# jtag_levelxlate.net
KiCad netlist of a schematic drawn in Altium Designer
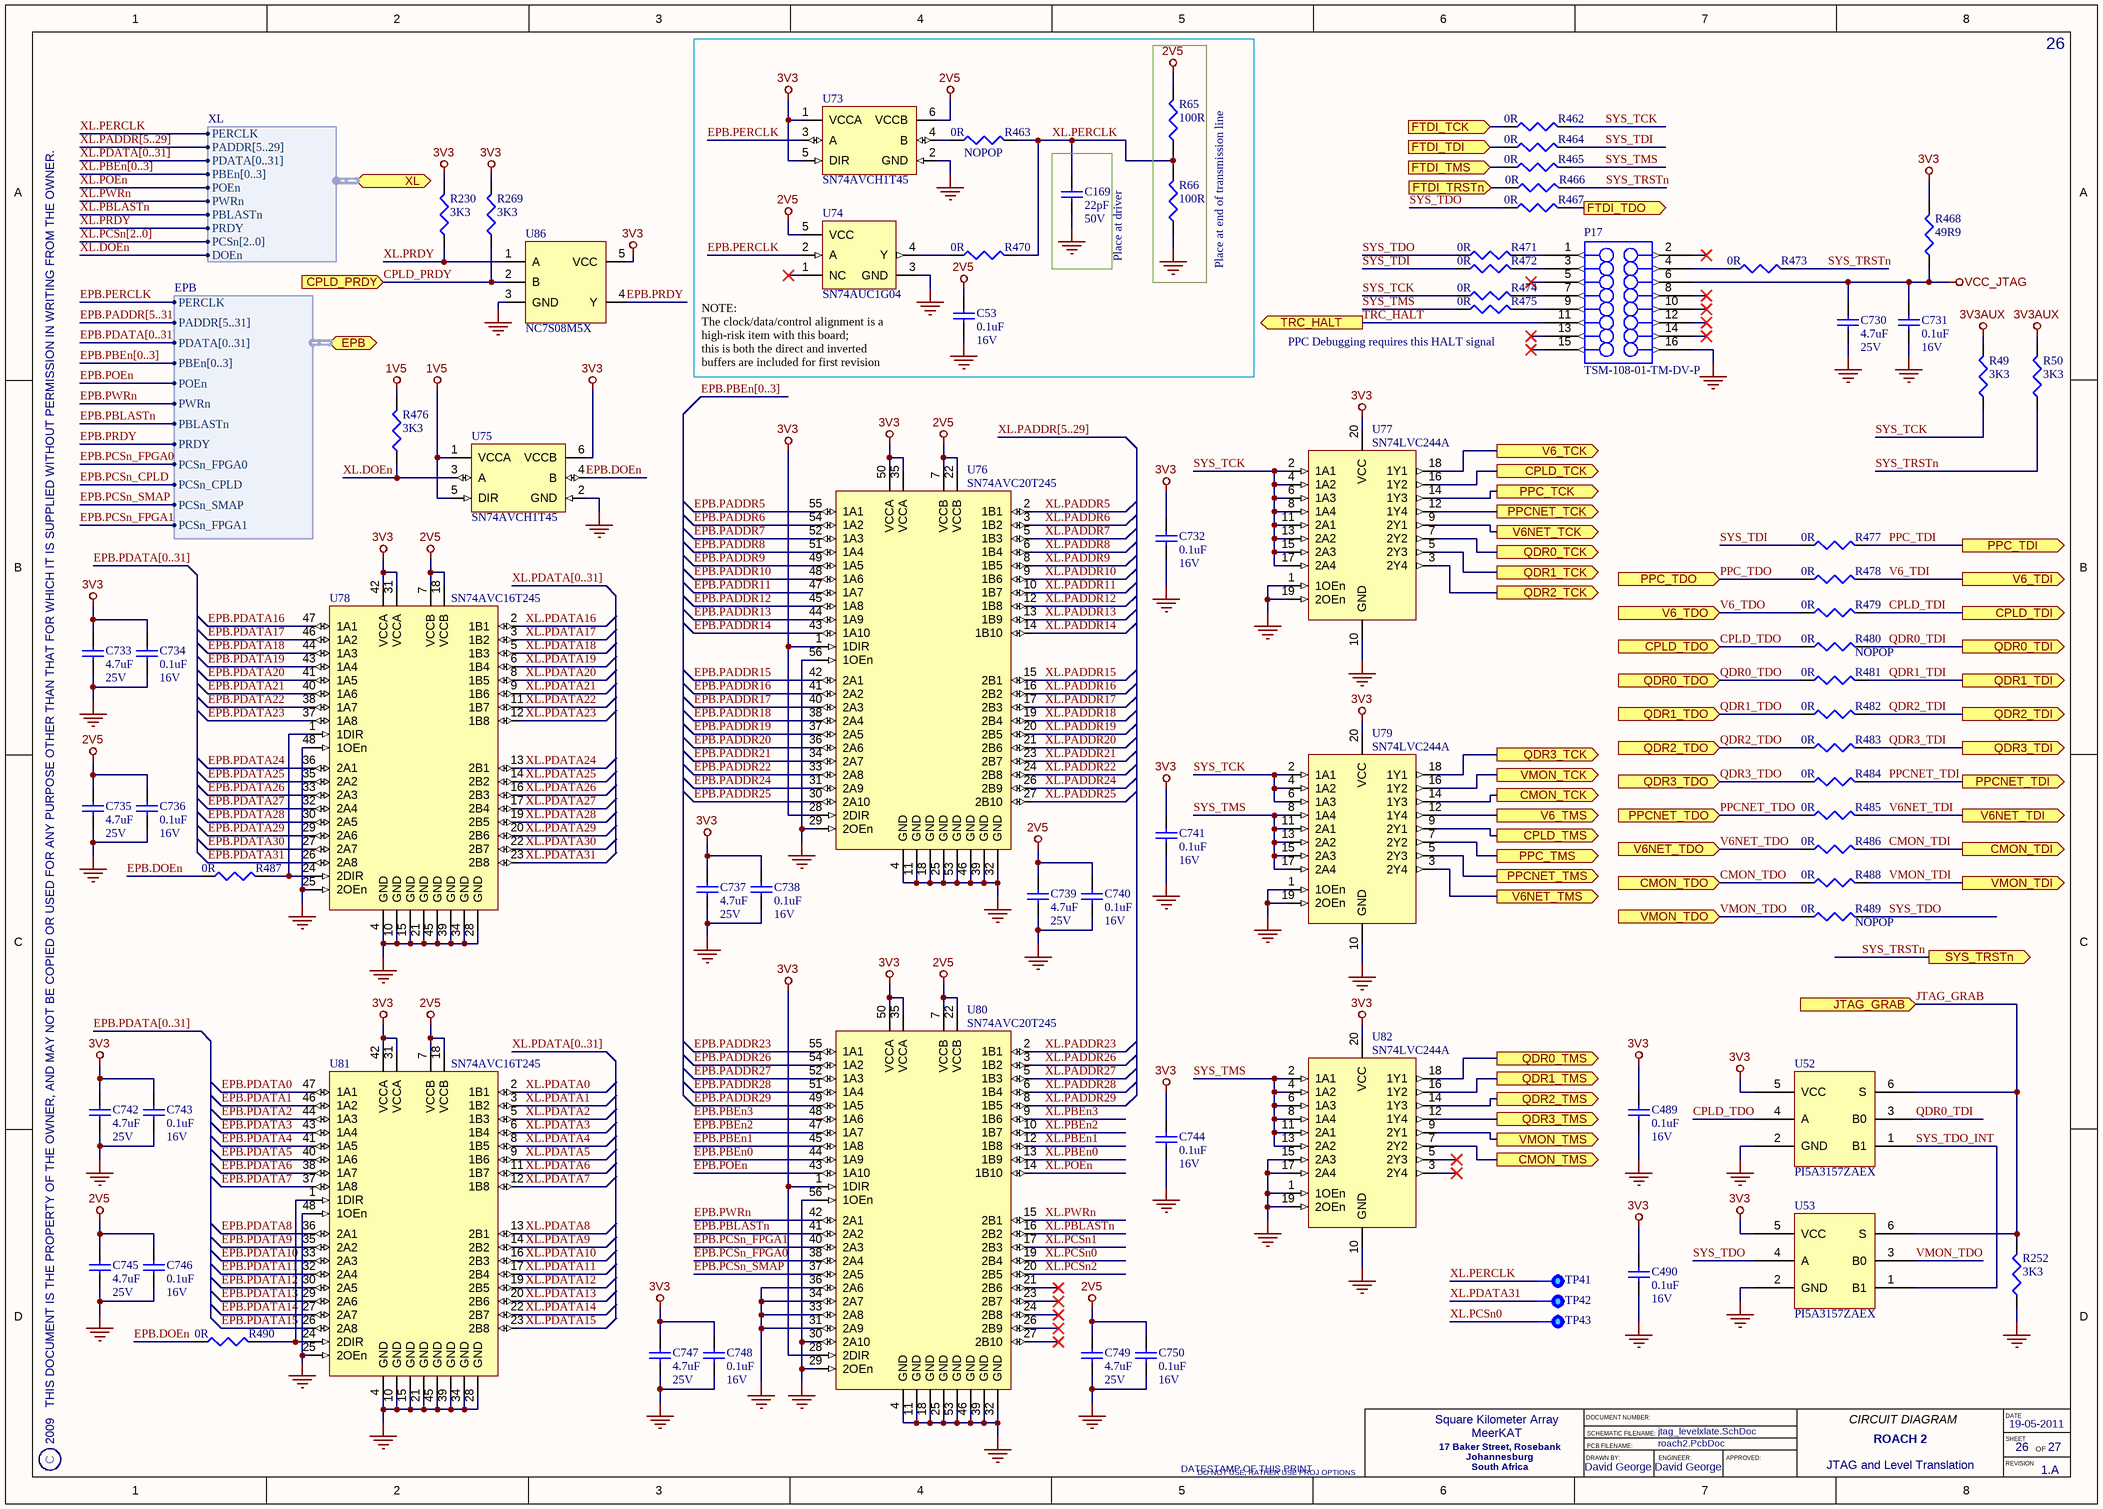
[diagram p0: jtag_levelxlate.SchDoc]

(export (version "E")
  (design (tool "Eeschema 10.0.6"))
  (components
    (comp (ref "C53")
      (value "0.1uF")
      (footprint "CAPC1005X60L")
      (description "0.1uF, Ceramic Capacitor")
      (fields
        (field (name "RATING") "16V")
        (field (name "MANUFACTURER") "VENKEL")
        (field (name "PARTNUM") "C0402X7R160-104KN")
      )
      (libsource (lib "altium_db") (part "CapStd"))
    )
    (comp (ref "C169")
      (value "22pF")
      (footprint "CAPC1005X55L")
      (description "22pF, Ceramic Capacitor")
      (fields
        (field (name "RATING") "50V")
        (field (name "MANUFACTURER") "MURATA")
        (field (name "PARTNUM") "GRM1555C1H220JZ01D")
      )
      (libsource (lib "altium_db") (part "CapStd"))
    )
    (comp (ref "C489")
      (value "0.1uF")
      (footprint "CAPC1005X60L")
      (description "0.1uF, Ceramic Capacitor")
      (fields
        (field (name "RATING") "16V")
        (field (name "MANUFACTURER") "VENKEL")
        (field (name "PARTNUM") "C0402X7R160-104KN")
      )
      (libsource (lib "altium_db") (part "CapStd"))
    )
    (comp (ref "C490")
      (value "0.1uF")
      (footprint "CAPC1005X60L")
      (description "0.1uF, Ceramic Capacitor")
      (fields
        (field (name "RATING") "16V")
        (field (name "MANUFACTURER") "VENKEL")
        (field (name "PARTNUM") "C0402X7R160-104KN")
      )
      (libsource (lib "altium_db") (part "CapStd"))
    )
    (comp (ref "C730")
      (value "4.7uF")
      (footprint "CAPC2012X127L")
      (description "4.7uF, Ceramic Capacitor")
      (fields
        (field (name "RATING") "25V")
        (field (name "MANUFACTURER") "MURATA")
        (field (name "PARTNUM") "GRM21BR61E475KA12K")
      )
      (libsource (lib "altium_db") (part "CapStd"))
    )
    (comp (ref "C731")
      (value "0.1uF")
      (footprint "CAPC1005X60L")
      (description "0.1uF, Ceramic Capacitor")
      (fields
        (field (name "RATING") "16V")
        (field (name "MANUFACTURER") "VENKEL")
        (field (name "PARTNUM") "C0402X7R160-104KN")
      )
      (libsource (lib "altium_db") (part "CapStd"))
    )
    (comp (ref "C732")
      (value "0.1uF")
      (footprint "CAPC1005X60L")
      (description "0.1uF, Ceramic Capacitor")
      (fields
        (field (name "RATING") "16V")
        (field (name "MANUFACTURER") "VENKEL")
        (field (name "PARTNUM") "C0402X7R160-104KN")
      )
      (libsource (lib "altium_db") (part "CapStd"))
    )
    (comp (ref "C733")
      (value "4.7uF")
      (footprint "CAPC2012X127L")
      (description "4.7uF, Ceramic Capacitor")
      (fields
        (field (name "RATING") "25V")
        (field (name "MANUFACTURER") "MURATA")
        (field (name "PARTNUM") "GRM21BR61E475KA12K")
      )
      (libsource (lib "altium_db") (part "CapStd"))
    )
    (comp (ref "C734")
      (value "0.1uF")
      (footprint "CAPC1005X60L")
      (description "0.1uF, Ceramic Capacitor")
      (fields
        (field (name "RATING") "16V")
        (field (name "MANUFACTURER") "VENKEL")
        (field (name "PARTNUM") "C0402X7R160-104KN")
      )
      (libsource (lib "altium_db") (part "CapStd"))
    )
    (comp (ref "C735")
      (value "4.7uF")
      (footprint "CAPC2012X127L")
      (description "4.7uF, Ceramic Capacitor")
      (fields
        (field (name "RATING") "25V")
        (field (name "MANUFACTURER") "MURATA")
        (field (name "PARTNUM") "GRM21BR61E475KA12K")
      )
      (libsource (lib "altium_db") (part "CapStd"))
    )
    (comp (ref "C736")
      (value "0.1uF")
      (footprint "CAPC1005X60L")
      (description "0.1uF, Ceramic Capacitor")
      (fields
        (field (name "RATING") "16V")
        (field (name "MANUFACTURER") "VENKEL")
        (field (name "PARTNUM") "C0402X7R160-104KN")
      )
      (libsource (lib "altium_db") (part "CapStd"))
    )
    (comp (ref "C737")
      (value "4.7uF")
      (footprint "CAPC2012X127L")
      (description "4.7uF, Ceramic Capacitor")
      (fields
        (field (name "RATING") "25V")
        (field (name "MANUFACTURER") "MURATA")
        (field (name "PARTNUM") "GRM21BR61E475KA12K")
      )
      (libsource (lib "altium_db") (part "CapStd"))
    )
    (comp (ref "C738")
      (value "0.1uF")
      (footprint "CAPC1005X60L")
      (description "0.1uF, Ceramic Capacitor")
      (fields
        (field (name "RATING") "16V")
        (field (name "MANUFACTURER") "VENKEL")
        (field (name "PARTNUM") "C0402X7R160-104KN")
      )
      (libsource (lib "altium_db") (part "CapStd"))
    )
    (comp (ref "C739")
      (value "4.7uF")
      (footprint "CAPC2012X127L")
      (description "4.7uF, Ceramic Capacitor")
      (fields
        (field (name "RATING") "25V")
        (field (name "MANUFACTURER") "MURATA")
        (field (name "PARTNUM") "GRM21BR61E475KA12K")
      )
      (libsource (lib "altium_db") (part "CapStd"))
    )
    (comp (ref "C740")
      (value "0.1uF")
      (footprint "CAPC1005X60L")
      (description "0.1uF, Ceramic Capacitor")
      (fields
        (field (name "RATING") "16V")
        (field (name "MANUFACTURER") "VENKEL")
        (field (name "PARTNUM") "C0402X7R160-104KN")
      )
      (libsource (lib "altium_db") (part "CapStd"))
    )
    (comp (ref "C741")
      (value "0.1uF")
      (footprint "CAPC1005X60L")
      (description "0.1uF, Ceramic Capacitor")
      (fields
        (field (name "RATING") "16V")
        (field (name "MANUFACTURER") "VENKEL")
        (field (name "PARTNUM") "C0402X7R160-104KN")
      )
      (libsource (lib "altium_db") (part "CapStd"))
    )
    (comp (ref "C742")
      (value "4.7uF")
      (footprint "CAPC2012X127L")
      (description "4.7uF, Ceramic Capacitor")
      (fields
        (field (name "RATING") "25V")
        (field (name "MANUFACTURER") "MURATA")
        (field (name "PARTNUM") "GRM21BR61E475KA12K")
      )
      (libsource (lib "altium_db") (part "CapStd"))
    )
    (comp (ref "C743")
      (value "0.1uF")
      (footprint "CAPC1005X60L")
      (description "0.1uF, Ceramic Capacitor")
      (fields
        (field (name "RATING") "16V")
        (field (name "MANUFACTURER") "VENKEL")
        (field (name "PARTNUM") "C0402X7R160-104KN")
      )
      (libsource (lib "altium_db") (part "CapStd"))
    )
    (comp (ref "C744")
      (value "0.1uF")
      (footprint "CAPC1005X60L")
      (description "0.1uF, Ceramic Capacitor")
      (fields
        (field (name "RATING") "16V")
        (field (name "MANUFACTURER") "VENKEL")
        (field (name "PARTNUM") "C0402X7R160-104KN")
      )
      (libsource (lib "altium_db") (part "CapStd"))
    )
    (comp (ref "C745")
      (value "4.7uF")
      (footprint "CAPC2012X127L")
      (description "4.7uF, Ceramic Capacitor")
      (fields
        (field (name "RATING") "25V")
        (field (name "MANUFACTURER") "MURATA")
        (field (name "PARTNUM") "GRM21BR61E475KA12K")
      )
      (libsource (lib "altium_db") (part "CapStd"))
    )
    (comp (ref "C746")
      (value "0.1uF")
      (footprint "CAPC1005X60L")
      (description "0.1uF, Ceramic Capacitor")
      (fields
        (field (name "RATING") "16V")
        (field (name "MANUFACTURER") "VENKEL")
        (field (name "PARTNUM") "C0402X7R160-104KN")
      )
      (libsource (lib "altium_db") (part "CapStd"))
    )
    (comp (ref "C747")
      (value "4.7uF")
      (footprint "CAPC2012X127L")
      (description "4.7uF, Ceramic Capacitor")
      (fields
        (field (name "RATING") "25V")
        (field (name "MANUFACTURER") "MURATA")
        (field (name "PARTNUM") "GRM21BR61E475KA12K")
      )
      (libsource (lib "altium_db") (part "CapStd"))
    )
    (comp (ref "C748")
      (value "0.1uF")
      (footprint "CAPC1005X60L")
      (description "0.1uF, Ceramic Capacitor")
      (fields
        (field (name "RATING") "16V")
        (field (name "MANUFACTURER") "VENKEL")
        (field (name "PARTNUM") "C0402X7R160-104KN")
      )
      (libsource (lib "altium_db") (part "CapStd"))
    )
    (comp (ref "C749")
      (value "4.7uF")
      (footprint "CAPC2012X127L")
      (description "4.7uF, Ceramic Capacitor")
      (fields
        (field (name "RATING") "25V")
        (field (name "MANUFACTURER") "MURATA")
        (field (name "PARTNUM") "GRM21BR61E475KA12K")
      )
      (libsource (lib "altium_db") (part "CapStd"))
    )
    (comp (ref "C750")
      (value "0.1uF")
      (footprint "CAPC1005X60L")
      (description "0.1uF, Ceramic Capacitor")
      (fields
        (field (name "RATING") "16V")
        (field (name "MANUFACTURER") "VENKEL")
        (field (name "PARTNUM") "C0402X7R160-104KN")
      )
      (libsource (lib "altium_db") (part "CapStd"))
    )
    (comp (ref "P17")
      (value "TSM-108-01-TM-DV-P")
      (footprint "SAMTEC_TSM-108-01-TM-DV-P")
      (description "2x8, 2.54 mm Pitch, Male Header")
      (fields (field (name "PARTNUM") "TSM-108-01-TM-DV-P") (field (name "MANUFACTURER") "SAMTEC"))
      (libsource (lib "altium_db") (part "con_hdr_2x8"))
    )
    (comp (ref "R49")
      (value "3K3")
      (footprint "RESC1005X40L")
      (description "3K3, 1.1mm x 0.5mm, Thick Film Resistor")
      (fields (field (name "MANUFACTURER") "ROYALOHM") (field (name "PARTNUM") "0402WGJ0332T1E"))
      (libsource (lib "altium_db") (part "ResStd"))
    )
    (comp (ref "R50")
      (value "3K3")
      (footprint "RESC1005X40L")
      (description "3K3, 1.1mm x 0.5mm, Thick Film Resistor")
      (fields (field (name "MANUFACTURER") "ROYALOHM") (field (name "PARTNUM") "0402WGJ0332T1E"))
      (libsource (lib "altium_db") (part "ResStd"))
    )
    (comp (ref "R65")
      (value "100R")
      (footprint "RESC1005X40L")
      (description "100R, 1.1mm x 0.5mm, Thick Film Resistor")
      (fields (field (name "MANUFACTURER") "ROYALOHM") (field (name "PARTNUM") "0402WGF0101T1E"))
      (libsource (lib "altium_db") (part "ResStd"))
    )
    (comp (ref "R66")
      (value "100R")
      (footprint "RESC1005X40L")
      (description "100R, 1.1mm x 0.5mm, Thick Film Resistor")
      (fields (field (name "MANUFACTURER") "ROYALOHM") (field (name "PARTNUM") "0402WGF0101T1E"))
      (libsource (lib "altium_db") (part "ResStd"))
    )
    (comp (ref "R230")
      (value "3K3")
      (footprint "RESC1005X40L")
      (description "3K3, 1.1mm x 0.5mm, Thick Film Resistor")
      (fields (field (name "MANUFACTURER") "ROYALOHM") (field (name "PARTNUM") "0402WGJ0332T1E"))
      (libsource (lib "altium_db") (part "ResStd"))
    )
    (comp (ref "R252")
      (value "3K3")
      (footprint "RESC1005X40L")
      (description "3K3, 1.1mm x 0.5mm, Thick Film Resistor")
      (fields (field (name "MANUFACTURER") "ROYALOHM") (field (name "PARTNUM") "0402WGJ0332T1E"))
      (libsource (lib "altium_db") (part "ResStd"))
    )
    (comp (ref "R269")
      (value "3K3")
      (footprint "RESC1005X40L")
      (description "3K3, 1.1mm x 0.5mm, Thick Film Resistor")
      (fields (field (name "MANUFACTURER") "ROYALOHM") (field (name "PARTNUM") "0402WGJ0332T1E"))
      (libsource (lib "altium_db") (part "ResStd"))
    )
    (comp (ref "R462")
      (value "0R")
      (footprint "RESC1005X40L")
      (description "0R, 1.1mm x 0.5mm, Thick Film Resistor")
      (fields (field (name "MANUFACTURER") "ROYALOHM") (field (name "PARTNUM") "0402WG00000T1E"))
      (libsource (lib "altium_db") (part "ResStd"))
    )
    (comp (ref "R463")
      (value "0R")
      (footprint "RESC1005X40L")
      (description "0R, 1.1mm x 0.5mm, Thick Film Resistor")
      (fields (field (name "MANUFACTURER") "ROYALOHM") (field (name "PARTNUM") "0402WG00000T1E"))
      (libsource (lib "altium_db") (part "ResStd"))
    )
    (comp (ref "R464")
      (value "0R")
      (footprint "RESC1005X40L")
      (description "0R, 1.1mm x 0.5mm, Thick Film Resistor")
      (fields (field (name "MANUFACTURER") "ROYALOHM") (field (name "PARTNUM") "0402WG00000T1E"))
      (libsource (lib "altium_db") (part "ResStd"))
    )
    (comp (ref "R465")
      (value "0R")
      (footprint "RESC1005X40L")
      (description "0R, 1.1mm x 0.5mm, Thick Film Resistor")
      (fields (field (name "MANUFACTURER") "ROYALOHM") (field (name "PARTNUM") "0402WG00000T1E"))
      (libsource (lib "altium_db") (part "ResStd"))
    )
    (comp (ref "R466")
      (value "0R")
      (footprint "RESC1005X40L")
      (description "0R, 1.1mm x 0.5mm, Thick Film Resistor")
      (fields (field (name "MANUFACTURER") "ROYALOHM") (field (name "PARTNUM") "0402WG00000T1E"))
      (libsource (lib "altium_db") (part "ResStd"))
    )
    (comp (ref "R467")
      (value "0R")
      (footprint "RESC1005X40L")
      (description "0R, 1.1mm x 0.5mm, Thick Film Resistor")
      (fields (field (name "MANUFACTURER") "ROYALOHM") (field (name "PARTNUM") "0402WG00000T1E"))
      (libsource (lib "altium_db") (part "ResStd"))
    )
    (comp (ref "R468")
      (value "49R9")
      (footprint "RESC1005X40L")
      (description "49R9, 1.1mm x 0.5mm, Thick Film Resistor")
      (fields (field (name "MANUFACTURER") "ROYALOHM") (field (name "PARTNUM") "0402WGF499JT1E"))
      (libsource (lib "altium_db") (part "ResStd"))
    )
    (comp (ref "R470")
      (value "0R")
      (footprint "RESC1005X40L")
      (description "0R, 1.1mm x 0.5mm, Thick Film Resistor")
      (fields (field (name "MANUFACTURER") "ROYALOHM") (field (name "PARTNUM") "0402WG00000T1E"))
      (libsource (lib "altium_db") (part "ResStd"))
    )
    (comp (ref "R471")
      (value "0R")
      (footprint "RESC1005X40L")
      (description "0R, 1.1mm x 0.5mm, Thick Film Resistor")
      (fields (field (name "MANUFACTURER") "ROYALOHM") (field (name "PARTNUM") "0402WG00000T1E"))
      (libsource (lib "altium_db") (part "ResStd"))
    )
    (comp (ref "R472")
      (value "0R")
      (footprint "RESC1005X40L")
      (description "0R, 1.1mm x 0.5mm, Thick Film Resistor")
      (fields (field (name "MANUFACTURER") "ROYALOHM") (field (name "PARTNUM") "0402WG00000T1E"))
      (libsource (lib "altium_db") (part "ResStd"))
    )
    (comp (ref "R473")
      (value "0R")
      (footprint "RESC1005X40L")
      (description "0R, 1.1mm x 0.5mm, Thick Film Resistor")
      (fields (field (name "MANUFACTURER") "ROYALOHM") (field (name "PARTNUM") "0402WG00000T1E"))
      (libsource (lib "altium_db") (part "ResStd"))
    )
    (comp (ref "R474")
      (value "0R")
      (footprint "RESC1005X40L")
      (description "0R, 1.1mm x 0.5mm, Thick Film Resistor")
      (fields (field (name "MANUFACTURER") "ROYALOHM") (field (name "PARTNUM") "0402WG00000T1E"))
      (libsource (lib "altium_db") (part "ResStd"))
    )
    (comp (ref "R475")
      (value "0R")
      (footprint "RESC1005X40L")
      (description "0R, 1.1mm x 0.5mm, Thick Film Resistor")
      (fields (field (name "MANUFACTURER") "ROYALOHM") (field (name "PARTNUM") "0402WG00000T1E"))
      (libsource (lib "altium_db") (part "ResStd"))
    )
    (comp (ref "R476")
      (value "3K3")
      (footprint "RESC1005X40L")
      (description "3K3, 1.1mm x 0.5mm, Thick Film Resistor")
      (fields (field (name "MANUFACTURER") "ROYALOHM") (field (name "PARTNUM") "0402WGJ0332T1E"))
      (libsource (lib "altium_db") (part "ResStd"))
    )
    (comp (ref "R477")
      (value "0R")
      (footprint "RESC1005X40L")
      (description "0R, 1.1mm x 0.5mm, Thick Film Resistor")
      (fields (field (name "MANUFACTURER") "ROYALOHM") (field (name "PARTNUM") "0402WG00000T1E"))
      (libsource (lib "altium_db") (part "ResStd"))
    )
    (comp (ref "R478")
      (value "0R")
      (footprint "RESC1005X40L")
      (description "0R, 1.1mm x 0.5mm, Thick Film Resistor")
      (fields (field (name "MANUFACTURER") "ROYALOHM") (field (name "PARTNUM") "0402WG00000T1E"))
      (libsource (lib "altium_db") (part "ResStd"))
    )
    (comp (ref "R479")
      (value "0R")
      (footprint "RESC1005X40L")
      (description "0R, 1.1mm x 0.5mm, Thick Film Resistor")
      (fields (field (name "MANUFACTURER") "ROYALOHM") (field (name "PARTNUM") "0402WG00000T1E"))
      (libsource (lib "altium_db") (part "ResStd"))
    )
    (comp (ref "R480")
      (value "0R")
      (footprint "RESC1005X40L")
      (description "0R, 1.1mm x 0.5mm, Thick Film Resistor")
      (fields (field (name "MANUFACTURER") "ROYALOHM") (field (name "PARTNUM") "0402WG00000T1E"))
      (libsource (lib "altium_db") (part "ResStd"))
    )
    (comp (ref "R481")
      (value "0R")
      (footprint "RESC1005X40L")
      (description "0R, 1.1mm x 0.5mm, Thick Film Resistor")
      (fields (field (name "MANUFACTURER") "ROYALOHM") (field (name "PARTNUM") "0402WG00000T1E"))
      (libsource (lib "altium_db") (part "ResStd"))
    )
    (comp (ref "R482")
      (value "0R")
      (footprint "RESC1005X40L")
      (description "0R, 1.1mm x 0.5mm, Thick Film Resistor")
      (fields (field (name "MANUFACTURER") "ROYALOHM") (field (name "PARTNUM") "0402WG00000T1E"))
      (libsource (lib "altium_db") (part "ResStd"))
    )
    (comp (ref "R483")
      (value "0R")
      (footprint "RESC1005X40L")
      (description "0R, 1.1mm x 0.5mm, Thick Film Resistor")
      (fields (field (name "MANUFACTURER") "ROYALOHM") (field (name "PARTNUM") "0402WG00000T1E"))
      (libsource (lib "altium_db") (part "ResStd"))
    )
    (comp (ref "R484")
      (value "0R")
      (footprint "RESC1005X40L")
      (description "0R, 1.1mm x 0.5mm, Thick Film Resistor")
      (fields (field (name "MANUFACTURER") "ROYALOHM") (field (name "PARTNUM") "0402WG00000T1E"))
      (libsource (lib "altium_db") (part "ResStd"))
    )
    (comp (ref "R485")
      (value "0R")
      (footprint "RESC1005X40L")
      (description "0R, 1.1mm x 0.5mm, Thick Film Resistor")
      (fields (field (name "MANUFACTURER") "ROYALOHM") (field (name "PARTNUM") "0402WG00000T1E"))
      (libsource (lib "altium_db") (part "ResStd"))
    )
    (comp (ref "R486")
      (value "0R")
      (footprint "RESC1005X40L")
      (description "0R, 1.1mm x 0.5mm, Thick Film Resistor")
      (fields (field (name "MANUFACTURER") "ROYALOHM") (field (name "PARTNUM") "0402WG00000T1E"))
      (libsource (lib "altium_db") (part "ResStd"))
    )
    (comp (ref "R487")
      (value "0R")
      (footprint "RESC1005X40L")
      (description "0R, 1.1mm x 0.5mm, Thick Film Resistor")
      (fields (field (name "MANUFACTURER") "ROYALOHM") (field (name "PARTNUM") "0402WG00000T1E"))
      (libsource (lib "altium_db") (part "ResStd"))
    )
    (comp (ref "R488")
      (value "0R")
      (footprint "RESC1005X40L")
      (description "0R, 1.1mm x 0.5mm, Thick Film Resistor")
      (fields (field (name "MANUFACTURER") "ROYALOHM") (field (name "PARTNUM") "0402WG00000T1E"))
      (libsource (lib "altium_db") (part "ResStd"))
    )
    (comp (ref "R489")
      (value "0R")
      (footprint "RESC1005X40L")
      (description "0R, 1.1mm x 0.5mm, Thick Film Resistor")
      (fields (field (name "MANUFACTURER") "ROYALOHM") (field (name "PARTNUM") "0402WG00000T1E"))
      (libsource (lib "altium_db") (part "ResStd"))
    )
    (comp (ref "R490")
      (value "0R")
      (footprint "RESC1005X40L")
      (description "0R, 1.1mm x 0.5mm, Thick Film Resistor")
      (fields (field (name "MANUFACTURER") "ROYALOHM") (field (name "PARTNUM") "0402WG00000T1E"))
      (libsource (lib "altium_db") (part "ResStd"))
    )
    (comp (ref "TP41")
      (value "Testpoint")
      (footprint "TP100")
      (description "1mm Diameter, through-hole, Circular Test-point")
      (libsource (lib "altium_db") (part "Testpoint"))
    )
    (comp (ref "TP42")
      (value "Testpoint")
      (footprint "TP100")
      (description "1mm Diameter, through-hole, Circular Test-point")
      (libsource (lib "altium_db") (part "Testpoint"))
    )
    (comp (ref "TP43")
      (value "Testpoint")
      (footprint "TP100")
      (description "1mm Diameter, through-hole, Circular Test-point")
      (libsource (lib "altium_db") (part "Testpoint"))
    )
    (comp (ref "U52")
      (value "PI5A3157ZAEX")
      (footprint "SC70-6")
      (description "Low voltage SPDT Analogue Switch")
      (fields (field (name "MANUFACTURER") "PERICOM"))
      (libsource (lib "altium_db") (part "PI5A3157ZAEX"))
    )
    (comp (ref "U53")
      (value "PI5A3157ZAEX")
      (footprint "SC70-6")
      (description "Low voltage SPDT Analogue Switch")
      (fields (field (name "MANUFACTURER") "PERICOM"))
      (libsource (lib "altium_db") (part "PI5A3157ZAEX"))
    )
    (comp (ref "U73")
      (value "SN74AVCH1T45")
      (footprint "SOT23-6")
      (description "Single-Bit Dual Supply Bus Transceiver with Configurable Voltage Translation and 3-State Outputs")
      (fields (field (name "MANUFACTURER") "Texas Instruments"))
      (libsource (lib "altium_db") (part "SN74AVCH1T45"))
    )
    (comp (ref "U74")
      (value "SN74AUC1G04")
      (footprint "SOT23-5")
      (description "Single Inverter Gate")
      (fields (field (name "MANUFACTURER") "Texas Instruments"))
      (libsource (lib "altium_db") (part "SN74AUC1G04"))
    )
    (comp (ref "U75")
      (value "SN74AVCH1T45")
      (footprint "SOT23-6")
      (description "Single-Bit Dual Supply Bus Transceiver with Configurable Voltage Translation and 3-State Outputs")
      (fields (field (name "MANUFACTURER") "Texas Instruments"))
      (libsource (lib "altium_db") (part "SN74AVCH1T45"))
    )
    (comp (ref "U76")
      (value "SN74AVC20T245")
      (footprint "PW056")
      (description "20-Bit Dual-Supply Bus Transceivers with Configurable Voltage Translation and 3-State Outputs")
      (fields (field (name "MANUFACTURER") "Texas Instruments"))
      (libsource (lib "altium_db") (part "SN74AVC20T245"))
    )
    (comp (ref "U77")
      (value "SN74LVC244A")
      (footprint "PW020")
      (description "Octal Buffer/Drive with 3-State Outputs")
      (fields (field (name "MANUFACTURER") "Texas Instruments"))
      (libsource (lib "altium_db") (part "SN74LVC244A"))
    )
    (comp (ref "U78")
      (value "SN74AVC16T245")
      (footprint "PW048")
      (description "16-BIT DUAL-SUPPLY BUS TRANSCEIVER WITH CONFIGURABLE VOLTAGE TRANSLATION AND 3-STATE OUTPUTS")
      (fields (field (name "MANUFACTURER") "Texas Instruments"))
      (libsource (lib "altium_db") (part "SN74AVC16T245"))
    )
    (comp (ref "U79")
      (value "SN74LVC244A")
      (footprint "PW020")
      (description "Octal Buffer/Drive with 3-State Outputs")
      (fields (field (name "MANUFACTURER") "Texas Instruments"))
      (libsource (lib "altium_db") (part "SN74LVC244A"))
    )
    (comp (ref "U80")
      (value "SN74AVC20T245")
      (footprint "PW056")
      (description "20-Bit Dual-Supply Bus Transceivers with Configurable Voltage Translation and 3-State Outputs")
      (fields (field (name "MANUFACTURER") "Texas Instruments"))
      (libsource (lib "altium_db") (part "SN74AVC20T245"))
    )
    (comp (ref "U81")
      (value "SN74AVC16T245")
      (footprint "PW048")
      (description "16-BIT DUAL-SUPPLY BUS TRANSCEIVER WITH CONFIGURABLE VOLTAGE TRANSLATION AND 3-STATE OUTPUTS")
      (fields (field (name "MANUFACTURER") "Texas Instruments"))
      (libsource (lib "altium_db") (part "SN74AVC16T245"))
    )
    (comp (ref "U82")
      (value "SN74LVC244A")
      (footprint "PW020")
      (description "Octal Buffer/Drive with 3-State Outputs")
      (fields (field (name "MANUFACTURER") "Texas Instruments"))
      (libsource (lib "altium_db") (part "SN74LVC244A"))
    )
    (comp (ref "U86")
      (value "NC7S08M5X")
      (footprint "SOT23-5")
      (description "TinyLogic® HS 2-Input AND Gate")
      (fields (field (name "MANUFACTURER") "Fairchild Semiconductor"))
      (libsource (lib "altium_db") (part "NC7S08"))
    )
  )
  (nets
    (net (code "5") (name "/CMON_TCK") (class "Default")
      (node (ref "U79") (pin "14") (pinfunction "1Y3_14") (pintype "output"))
    )
    (net (code "6") (name "/CMON_TDI") (class "Default")
      (node (ref "R486") (pin "2") (pinfunction "2_2") (pintype "passive"))
    )
    (net (code "7") (name "/CMON_TDO") (class "Default")
      (node (ref "R488") (pin "1") (pinfunction "1_1") (pintype "passive"))
    )
    (net (code "8") (name "/CMON_TMS") (class "Default")
      (node (ref "U82") (pin "7") (pinfunction "2Y2_7") (pintype "output"))
    )
    (net (code "9") (name "/CPLD_PRDY") (class "Default")
      (node (ref "R269") (pin "1") (pinfunction "1_1") (pintype "passive"))
      (node (ref "U86") (pin "2") (pinfunction "B_2") (pintype "passive"))
    )
    (net (code "10") (name "/CPLD_TCK") (class "Default")
      (node (ref "U77") (pin "16") (pinfunction "1Y2_16") (pintype "output"))
    )
    (net (code "11") (name "/CPLD_TDI") (class "Default")
      (node (ref "R479") (pin "2") (pinfunction "2_2") (pintype "passive"))
    )
    (net (code "12") (name "/CPLD_TDO") (class "Default")
      (node (ref "R480") (pin "1") (pinfunction "1_1") (pintype "passive"))
      (node (ref "U52") (pin "4") (pinfunction "A_4") (pintype "passive"))
    )
    (net (code "13") (name "/CPLD_TMS") (class "Default")
      (node (ref "U79") (pin "9") (pinfunction "2Y1_9") (pintype "output"))
    )
    (net (code "14") (name "/EPB.DOEn") (class "Default")
      (node (ref "R487") (pin "1") (pinfunction "1_1") (pintype "passive"))
      (node (ref "R490") (pin "1") (pinfunction "1_1") (pintype "passive"))
      (node (ref "U75") (pin "4") (pinfunction "B_4") (pintype "bidirectional"))
    )
    (net (code "15") (name "/EPB.PADDR5") (class "Default")
      (node (ref "U76") (pin "55") (pinfunction "1A1_55") (pintype "bidirectional"))
    )
    (net (code "16") (name "/EPB.PADDR6") (class "Default")
      (node (ref "U76") (pin "54") (pinfunction "1A2_54") (pintype "bidirectional"))
    )
    (net (code "17") (name "/EPB.PADDR7") (class "Default")
      (node (ref "U76") (pin "52") (pinfunction "1A3_52") (pintype "bidirectional"))
    )
    (net (code "18") (name "/EPB.PADDR8") (class "Default")
      (node (ref "U76") (pin "51") (pinfunction "1A4_51") (pintype "bidirectional"))
    )
    (net (code "19") (name "/EPB.PADDR9") (class "Default")
      (node (ref "U76") (pin "49") (pinfunction "1A5_49") (pintype "bidirectional"))
    )
    (net (code "20") (name "/EPB.PADDR10") (class "Default")
      (node (ref "U76") (pin "48") (pinfunction "1A6_48") (pintype "bidirectional"))
    )
    (net (code "21") (name "/EPB.PADDR11") (class "Default")
      (node (ref "U76") (pin "47") (pinfunction "1A7_47") (pintype "bidirectional"))
    )
    (net (code "22") (name "/EPB.PADDR12") (class "Default")
      (node (ref "U76") (pin "45") (pinfunction "1A8_45") (pintype "bidirectional"))
    )
    (net (code "23") (name "/EPB.PADDR13") (class "Default")
      (node (ref "U76") (pin "44") (pinfunction "1A9_44") (pintype "bidirectional"))
    )
    (net (code "24") (name "/EPB.PADDR14") (class "Default")
      (node (ref "U76") (pin "43") (pinfunction "1A10_43") (pintype "bidirectional"))
    )
    (net (code "25") (name "/EPB.PADDR15") (class "Default")
      (node (ref "U76") (pin "42") (pinfunction "2A1_42") (pintype "bidirectional"))
    )
    (net (code "26") (name "/EPB.PADDR16") (class "Default")
      (node (ref "U76") (pin "41") (pinfunction "2A2_41") (pintype "bidirectional"))
    )
    (net (code "27") (name "/EPB.PADDR17") (class "Default")
      (node (ref "U76") (pin "40") (pinfunction "2A3_40") (pintype "bidirectional"))
    )
    (net (code "28") (name "/EPB.PADDR18") (class "Default")
      (node (ref "U76") (pin "38") (pinfunction "2A4_38") (pintype "bidirectional"))
    )
    (net (code "29") (name "/EPB.PADDR19") (class "Default")
      (node (ref "U76") (pin "37") (pinfunction "2A5_37") (pintype "bidirectional"))
    )
    (net (code "30") (name "/EPB.PADDR20") (class "Default")
      (node (ref "U76") (pin "36") (pinfunction "2A6_36") (pintype "bidirectional"))
    )
    (net (code "31") (name "/EPB.PADDR21") (class "Default")
      (node (ref "U76") (pin "34") (pinfunction "2A7_34") (pintype "bidirectional"))
    )
    (net (code "32") (name "/EPB.PADDR22") (class "Default")
      (node (ref "U76") (pin "33") (pinfunction "2A8_33") (pintype "bidirectional"))
    )
    (net (code "33") (name "/EPB.PADDR23") (class "Default")
      (node (ref "U80") (pin "55") (pinfunction "1A1_55") (pintype "bidirectional"))
    )
    (net (code "34") (name "/EPB.PADDR24") (class "Default")
      (node (ref "U76") (pin "31") (pinfunction "2A9_31") (pintype "bidirectional"))
    )
    (net (code "35") (name "/EPB.PADDR25") (class "Default")
      (node (ref "U76") (pin "30") (pinfunction "2A10_30") (pintype "bidirectional"))
    )
    (net (code "36") (name "/EPB.PADDR26") (class "Default")
      (node (ref "U80") (pin "54") (pinfunction "1A2_54") (pintype "bidirectional"))
    )
    (net (code "37") (name "/EPB.PADDR27") (class "Default")
      (node (ref "U80") (pin "52") (pinfunction "1A3_52") (pintype "bidirectional"))
    )
    (net (code "38") (name "/EPB.PADDR28") (class "Default")
      (node (ref "U80") (pin "51") (pinfunction "1A4_51") (pintype "bidirectional"))
    )
    (net (code "39") (name "/EPB.PADDR29") (class "Default")
      (node (ref "U80") (pin "49") (pinfunction "1A5_49") (pintype "bidirectional"))
    )
    (net (code "41") (name "/EPB.PBEn0") (class "Default")
      (node (ref "U80") (pin "44") (pinfunction "1A9_44") (pintype "bidirectional"))
    )
    (net (code "42") (name "/EPB.PBEn1") (class "Default")
      (node (ref "U80") (pin "45") (pinfunction "1A8_45") (pintype "bidirectional"))
    )
    (net (code "43") (name "/EPB.PBEn2") (class "Default")
      (node (ref "U80") (pin "47") (pinfunction "1A7_47") (pintype "bidirectional"))
    )
    (net (code "44") (name "/EPB.PBEn3") (class "Default")
      (node (ref "U80") (pin "48") (pinfunction "1A6_48") (pintype "bidirectional"))
    )
    (net (code "46") (name "/EPB.PBLASTn") (class "Default")
      (node (ref "U80") (pin "41") (pinfunction "2A2_41") (pintype "bidirectional"))
    )
    (net (code "48") (name "/EPB.PCSn_FPGA0") (class "Default")
      (node (ref "U80") (pin "38") (pinfunction "2A4_38") (pintype "bidirectional"))
    )
    (net (code "49") (name "/EPB.PCSn_FPGA1") (class "Default")
      (node (ref "U80") (pin "40") (pinfunction "2A3_40") (pintype "bidirectional"))
    )
    (net (code "50") (name "/EPB.PCSn_SMAP") (class "Default")
      (node (ref "U80") (pin "37") (pinfunction "2A5_37") (pintype "bidirectional"))
    )
    (net (code "51") (name "/EPB.PDATA0") (class "Default")
      (node (ref "U81") (pin "47") (pinfunction "1A1_47") (pintype "bidirectional"))
    )
    (net (code "52") (name "/EPB.PDATA1") (class "Default")
      (node (ref "U81") (pin "46") (pinfunction "1A2_46") (pintype "bidirectional"))
    )
    (net (code "53") (name "/EPB.PDATA2") (class "Default")
      (node (ref "U81") (pin "44") (pinfunction "1A3_44") (pintype "bidirectional"))
    )
    (net (code "54") (name "/EPB.PDATA3") (class "Default")
      (node (ref "U81") (pin "43") (pinfunction "1A4_43") (pintype "bidirectional"))
    )
    (net (code "55") (name "/EPB.PDATA4") (class "Default")
      (node (ref "U81") (pin "41") (pinfunction "1A5_41") (pintype "bidirectional"))
    )
    (net (code "56") (name "/EPB.PDATA5") (class "Default")
      (node (ref "U81") (pin "40") (pinfunction "1A6_40") (pintype "bidirectional"))
    )
    (net (code "57") (name "/EPB.PDATA6") (class "Default")
      (node (ref "U81") (pin "38") (pinfunction "1A7_38") (pintype "bidirectional"))
    )
    (net (code "58") (name "/EPB.PDATA7") (class "Default")
      (node (ref "U81") (pin "37") (pinfunction "1A8_37") (pintype "bidirectional"))
    )
    (net (code "59") (name "/EPB.PDATA8") (class "Default")
      (node (ref "U81") (pin "36") (pinfunction "2A1_36") (pintype "bidirectional"))
    )
    (net (code "60") (name "/EPB.PDATA9") (class "Default")
      (node (ref "U81") (pin "35") (pinfunction "2A2_35") (pintype "bidirectional"))
    )
    (net (code "61") (name "/EPB.PDATA10") (class "Default")
      (node (ref "U81") (pin "33") (pinfunction "2A3_33") (pintype "bidirectional"))
    )
    (net (code "62") (name "/EPB.PDATA11") (class "Default")
      (node (ref "U81") (pin "32") (pinfunction "2A4_32") (pintype "bidirectional"))
    )
    (net (code "63") (name "/EPB.PDATA12") (class "Default")
      (node (ref "U81") (pin "30") (pinfunction "2A5_30") (pintype "bidirectional"))
    )
    (net (code "64") (name "/EPB.PDATA13") (class "Default")
      (node (ref "U81") (pin "29") (pinfunction "2A6_29") (pintype "bidirectional"))
    )
    (net (code "65") (name "/EPB.PDATA14") (class "Default")
      (node (ref "U81") (pin "27") (pinfunction "2A7_27") (pintype "bidirectional"))
    )
    (net (code "66") (name "/EPB.PDATA15") (class "Default")
      (node (ref "U81") (pin "26") (pinfunction "2A8_26") (pintype "bidirectional"))
    )
    (net (code "67") (name "/EPB.PDATA16") (class "Default")
      (node (ref "U78") (pin "47") (pinfunction "1A1_47") (pintype "bidirectional"))
    )
    (net (code "68") (name "/EPB.PDATA17") (class "Default")
      (node (ref "U78") (pin "46") (pinfunction "1A2_46") (pintype "bidirectional"))
    )
    (net (code "69") (name "/EPB.PDATA18") (class "Default")
      (node (ref "U78") (pin "44") (pinfunction "1A3_44") (pintype "bidirectional"))
    )
    (net (code "70") (name "/EPB.PDATA19") (class "Default")
      (node (ref "U78") (pin "43") (pinfunction "1A4_43") (pintype "bidirectional"))
    )
    (net (code "71") (name "/EPB.PDATA20") (class "Default")
      (node (ref "U78") (pin "41") (pinfunction "1A5_41") (pintype "bidirectional"))
    )
    (net (code "72") (name "/EPB.PDATA21") (class "Default")
      (node (ref "U78") (pin "40") (pinfunction "1A6_40") (pintype "bidirectional"))
    )
    (net (code "73") (name "/EPB.PDATA22") (class "Default")
      (node (ref "U78") (pin "38") (pinfunction "1A7_38") (pintype "bidirectional"))
    )
    (net (code "74") (name "/EPB.PDATA23") (class "Default")
      (node (ref "U78") (pin "37") (pinfunction "1A8_37") (pintype "bidirectional"))
    )
    (net (code "75") (name "/EPB.PDATA24") (class "Default")
      (node (ref "U78") (pin "36") (pinfunction "2A1_36") (pintype "bidirectional"))
    )
    (net (code "76") (name "/EPB.PDATA25") (class "Default")
      (node (ref "U78") (pin "35") (pinfunction "2A2_35") (pintype "bidirectional"))
    )
    (net (code "77") (name "/EPB.PDATA26") (class "Default")
      (node (ref "U78") (pin "33") (pinfunction "2A3_33") (pintype "bidirectional"))
    )
    (net (code "78") (name "/EPB.PDATA27") (class "Default")
      (node (ref "U78") (pin "32") (pinfunction "2A4_32") (pintype "bidirectional"))
    )
    (net (code "79") (name "/EPB.PDATA28") (class "Default")
      (node (ref "U78") (pin "30") (pinfunction "2A5_30") (pintype "bidirectional"))
    )
    (net (code "80") (name "/EPB.PDATA29") (class "Default")
      (node (ref "U78") (pin "29") (pinfunction "2A6_29") (pintype "bidirectional"))
    )
    (net (code "81") (name "/EPB.PDATA30") (class "Default")
      (node (ref "U78") (pin "27") (pinfunction "2A7_27") (pintype "bidirectional"))
    )
    (net (code "82") (name "/EPB.PDATA31") (class "Default")
      (node (ref "U78") (pin "26") (pinfunction "2A8_26") (pintype "bidirectional"))
    )
    (net (code "84") (name "/EPB.PERCLK") (class "Default")
      (node (ref "U73") (pin "3") (pinfunction "A_3") (pintype "bidirectional"))
      (node (ref "U74") (pin "2") (pinfunction "A_2") (pintype "input"))
    )
    (net (code "85") (name "/EPB.POEn") (class "Default")
      (node (ref "U80") (pin "43") (pinfunction "1A10_43") (pintype "bidirectional"))
    )
    (net (code "86") (name "/EPB.PRDY") (class "Default")
      (node (ref "U86") (pin "4") (pinfunction "Y_4") (pintype "passive"))
    )
    (net (code "87") (name "/EPB.PWRn") (class "Default")
      (node (ref "U80") (pin "42") (pinfunction "2A1_42") (pintype "bidirectional"))
    )
    (net (code "88") (name "/FTDI_TCK") (class "Default")
      (node (ref "R462") (pin "1") (pinfunction "1_1") (pintype "passive"))
    )
    (net (code "89") (name "/FTDI_TDI") (class "Default")
      (node (ref "R464") (pin "1") (pinfunction "1_1") (pintype "passive"))
    )
    (net (code "90") (name "/FTDI_TDO") (class "Default")
      (node (ref "R467") (pin "2") (pinfunction "2_2") (pintype "passive"))
    )
    (net (code "91") (name "/FTDI_TMS") (class "Default")
      (node (ref "R465") (pin "1") (pinfunction "1_1") (pintype "passive"))
    )
    (net (code "92") (name "/FTDI_TRSTn") (class "Default")
      (node (ref "R466") (pin "1") (pinfunction "1_1") (pintype "passive"))
    )
    (net (code "93") (name "/JTAG_GRAB") (class "Default")
      (node (ref "R252") (pin "2") (pinfunction "2_2") (pintype "passive"))
      (node (ref "U52") (pin "6") (pinfunction "S_6") (pintype "passive"))
      (node (ref "U53") (pin "6") (pinfunction "S_6") (pintype "passive"))
    )
    (net (code "94") (name "/PPCNET_TCK") (class "Default")
      (node (ref "U77") (pin "12") (pinfunction "1Y4_12") (pintype "output"))
    )
    (net (code "95") (name "/PPCNET_TDI") (class "Default")
      (node (ref "R484") (pin "2") (pinfunction "2_2") (pintype "passive"))
    )
    (net (code "96") (name "/PPCNET_TDO") (class "Default")
      (node (ref "R485") (pin "1") (pinfunction "1_1") (pintype "passive"))
    )
    (net (code "97") (name "/PPCNET_TMS") (class "Default")
      (node (ref "U79") (pin "5") (pinfunction "2Y3_5") (pintype "output"))
    )
    (net (code "98") (name "/PPC_TCK") (class "Default")
      (node (ref "U77") (pin "14") (pinfunction "1Y3_14") (pintype "output"))
    )
    (net (code "99") (name "/PPC_TDI") (class "Default")
      (node (ref "R477") (pin "2") (pinfunction "2_2") (pintype "passive"))
    )
    (net (code "100") (name "/PPC_TDO") (class "Default")
      (node (ref "R478") (pin "1") (pinfunction "1_1") (pintype "passive"))
    )
    (net (code "101") (name "/PPC_TMS") (class "Default")
      (node (ref "U79") (pin "7") (pinfunction "2Y2_7") (pintype "output"))
    )
    (net (code "102") (name "/QDR0_TCK") (class "Default")
      (node (ref "U77") (pin "7") (pinfunction "2Y2_7") (pintype "output"))
    )
    (net (code "103") (name "/QDR0_TDI") (class "Default")
      (node (ref "R480") (pin "2") (pinfunction "2_2") (pintype "passive"))
      (node (ref "U52") (pin "3") (pinfunction "B0_3") (pintype "passive"))
    )
    (net (code "104") (name "/QDR0_TDO") (class "Default")
      (node (ref "R481") (pin "1") (pinfunction "1_1") (pintype "passive"))
    )
    (net (code "105") (name "/QDR0_TMS") (class "Default")
      (node (ref "U82") (pin "18") (pinfunction "1Y1_18") (pintype "output"))
    )
    (net (code "106") (name "/QDR1_TCK") (class "Default")
      (node (ref "U77") (pin "5") (pinfunction "2Y3_5") (pintype "output"))
    )
    (net (code "107") (name "/QDR1_TDI") (class "Default")
      (node (ref "R481") (pin "2") (pinfunction "2_2") (pintype "passive"))
    )
    (net (code "108") (name "/QDR1_TDO") (class "Default")
      (node (ref "R482") (pin "1") (pinfunction "1_1") (pintype "passive"))
    )
    (net (code "109") (name "/QDR1_TMS") (class "Default")
      (node (ref "U82") (pin "16") (pinfunction "1Y2_16") (pintype "output"))
    )
    (net (code "110") (name "/QDR2_TCK") (class "Default")
      (node (ref "U77") (pin "3") (pinfunction "2Y4_3") (pintype "output"))
    )
    (net (code "111") (name "/QDR2_TDI") (class "Default")
      (node (ref "R482") (pin "2") (pinfunction "2_2") (pintype "passive"))
    )
    (net (code "112") (name "/QDR2_TDO") (class "Default")
      (node (ref "R483") (pin "1") (pinfunction "1_1") (pintype "passive"))
    )
    (net (code "113") (name "/QDR2_TMS") (class "Default")
      (node (ref "U82") (pin "14") (pinfunction "1Y3_14") (pintype "output"))
    )
    (net (code "114") (name "/QDR3_TCK") (class "Default")
      (node (ref "U79") (pin "18") (pinfunction "1Y1_18") (pintype "output"))
    )
    (net (code "115") (name "/QDR3_TDI") (class "Default")
      (node (ref "R483") (pin "2") (pinfunction "2_2") (pintype "passive"))
    )
    (net (code "116") (name "/QDR3_TDO") (class "Default")
      (node (ref "R484") (pin "1") (pinfunction "1_1") (pintype "passive"))
    )
    (net (code "117") (name "/QDR3_TMS") (class "Default")
      (node (ref "U82") (pin "12") (pinfunction "1Y4_12") (pintype "output"))
    )
    (net (code "118") (name "/SYS_TCK") (class "Default")
      (node (ref "R462") (pin "2") (pinfunction "2_2") (pintype "passive"))
      (node (ref "R474") (pin "1") (pinfunction "1_1") (pintype "passive"))
      (node (ref "R49") (pin "1") (pinfunction "1_1") (pintype "passive"))
      (node (ref "U77") (pin "11") (pinfunction "2A1_11") (pintype "input"))
      (node (ref "U77") (pin "13") (pinfunction "2A2_13") (pintype "input"))
      (node (ref "U77") (pin "15") (pinfunction "2A3_15") (pintype "input"))
      (node (ref "U77") (pin "17") (pinfunction "2A4_17") (pintype "input"))
      (node (ref "U77") (pin "2") (pinfunction "1A1_2") (pintype "input"))
      (node (ref "U77") (pin "4") (pinfunction "1A2_4") (pintype "input"))
      (node (ref "U77") (pin "6") (pinfunction "1A3_6") (pintype "input"))
      (node (ref "U77") (pin "8") (pinfunction "1A4_8") (pintype "input"))
      (node (ref "U79") (pin "2") (pinfunction "1A1_2") (pintype "input"))
      (node (ref "U79") (pin "4") (pinfunction "1A2_4") (pintype "input"))
      (node (ref "U79") (pin "6") (pinfunction "1A3_6") (pintype "input"))
    )
    (net (code "119") (name "/SYS_TDI") (class "Default")
      (node (ref "R464") (pin "2") (pinfunction "2_2") (pintype "passive"))
      (node (ref "R472") (pin "1") (pinfunction "1_1") (pintype "passive"))
      (node (ref "R477") (pin "1") (pinfunction "1_1") (pintype "passive"))
    )
    (net (code "120") (name "/SYS_TDO") (class "Default")
      (node (ref "R467") (pin "1") (pinfunction "1_1") (pintype "passive"))
      (node (ref "R471") (pin "1") (pinfunction "1_1") (pintype "passive"))
      (node (ref "R489") (pin "2") (pinfunction "2_2") (pintype "passive"))
      (node (ref "U53") (pin "4") (pinfunction "A_4") (pintype "passive"))
    )
    (net (code "121") (name "/SYS_TDO_INT") (class "Default")
      (node (ref "U52") (pin "1") (pinfunction "B1_1") (pintype "passive"))
      (node (ref "U53") (pin "1") (pinfunction "B1_1") (pintype "passive"))
    )
    (net (code "122") (name "/SYS_TMS") (class "Default")
      (node (ref "R465") (pin "2") (pinfunction "2_2") (pintype "passive"))
      (node (ref "R475") (pin "1") (pinfunction "1_1") (pintype "passive"))
      (node (ref "U79") (pin "11") (pinfunction "2A1_11") (pintype "input"))
      (node (ref "U79") (pin "13") (pinfunction "2A2_13") (pintype "input"))
      (node (ref "U79") (pin "15") (pinfunction "2A3_15") (pintype "input"))
      (node (ref "U79") (pin "17") (pinfunction "2A4_17") (pintype "input"))
      (node (ref "U79") (pin "8") (pinfunction "1A4_8") (pintype "input"))
      (node (ref "U82") (pin "11") (pinfunction "2A1_11") (pintype "input"))
      (node (ref "U82") (pin "13") (pinfunction "2A2_13") (pintype "input"))
      (node (ref "U82") (pin "2") (pinfunction "1A1_2") (pintype "input"))
      (node (ref "U82") (pin "4") (pinfunction "1A2_4") (pintype "input"))
      (node (ref "U82") (pin "6") (pinfunction "1A3_6") (pintype "input"))
      (node (ref "U82") (pin "8") (pinfunction "1A4_8") (pintype "input"))
    )
    (net (code "123") (name "/SYS_TRSTn") (class "Default")
      (node (ref "R466") (pin "2") (pinfunction "2_2") (pintype "passive"))
      (node (ref "R473") (pin "2") (pinfunction "2_2") (pintype "passive"))
      (node (ref "R50") (pin "1") (pinfunction "1_1") (pintype "passive"))
    )
    (net (code "124") (name "/TRC_HALT") (class "Default")
      (node (ref "P17") (pin "11") (pinfunction "A11_11") (pintype "output"))
    )
    (net (code "125") (name "/V6NET_TCK") (class "Default")
      (node (ref "U77") (pin "9") (pinfunction "2Y1_9") (pintype "output"))
    )
    (net (code "126") (name "/V6NET_TDI") (class "Default")
      (node (ref "R485") (pin "2") (pinfunction "2_2") (pintype "passive"))
    )
    (net (code "127") (name "/V6NET_TDO") (class "Default")
      (node (ref "R486") (pin "1") (pinfunction "1_1") (pintype "passive"))
    )
    (net (code "128") (name "/V6NET_TMS") (class "Default")
      (node (ref "U79") (pin "3") (pinfunction "2Y4_3") (pintype "output"))
    )
    (net (code "129") (name "/V6_TCK") (class "Default")
      (node (ref "U77") (pin "18") (pinfunction "1Y1_18") (pintype "output"))
    )
    (net (code "130") (name "/V6_TDI") (class "Default")
      (node (ref "R478") (pin "2") (pinfunction "2_2") (pintype "passive"))
    )
    (net (code "131") (name "/V6_TDO") (class "Default")
      (node (ref "R479") (pin "1") (pinfunction "1_1") (pintype "passive"))
    )
    (net (code "132") (name "/V6_TMS") (class "Default")
      (node (ref "U79") (pin "12") (pinfunction "1Y4_12") (pintype "output"))
    )
    (net (code "133") (name "/VMON_TCK") (class "Default")
      (node (ref "U79") (pin "16") (pinfunction "1Y2_16") (pintype "output"))
    )
    (net (code "134") (name "/VMON_TDI") (class "Default")
      (node (ref "R488") (pin "2") (pinfunction "2_2") (pintype "passive"))
    )
    (net (code "135") (name "/VMON_TDO") (class "Default")
      (node (ref "R489") (pin "1") (pinfunction "1_1") (pintype "passive"))
      (node (ref "U53") (pin "3") (pinfunction "B0_3") (pintype "passive"))
    )
    (net (code "136") (name "/VMON_TMS") (class "Default")
      (node (ref "U82") (pin "9") (pinfunction "2Y1_9") (pintype "output"))
    )
    (net (code "137") (name "/XL.DOEn") (class "Default")
      (node (ref "R476") (pin "1") (pinfunction "1_1") (pintype "passive"))
      (node (ref "U75") (pin "3") (pinfunction "A_3") (pintype "bidirectional"))
    )
    (net (code "138") (name "/XL.PADDR5") (class "Default")
      (node (ref "U76") (pin "2") (pinfunction "1B1_2") (pintype "bidirectional"))
    )
    (net (code "139") (name "/XL.PADDR6") (class "Default")
      (node (ref "U76") (pin "3") (pinfunction "1B2_3") (pintype "bidirectional"))
    )
    (net (code "140") (name "/XL.PADDR7") (class "Default")
      (node (ref "U76") (pin "5") (pinfunction "1B3_5") (pintype "bidirectional"))
    )
    (net (code "141") (name "/XL.PADDR8") (class "Default")
      (node (ref "U76") (pin "6") (pinfunction "1B4_6") (pintype "bidirectional"))
    )
    (net (code "142") (name "/XL.PADDR9") (class "Default")
      (node (ref "U76") (pin "8") (pinfunction "1B5_8") (pintype "bidirectional"))
    )
    (net (code "143") (name "/XL.PADDR10") (class "Default")
      (node (ref "U76") (pin "9") (pinfunction "1B6_9") (pintype "bidirectional"))
    )
    (net (code "144") (name "/XL.PADDR11") (class "Default")
      (node (ref "U76") (pin "10") (pinfunction "1B7_10") (pintype "bidirectional"))
    )
    (net (code "145") (name "/XL.PADDR12") (class "Default")
      (node (ref "U76") (pin "12") (pinfunction "1B8_12") (pintype "bidirectional"))
    )
    (net (code "146") (name "/XL.PADDR13") (class "Default")
      (node (ref "U76") (pin "13") (pinfunction "1B9_13") (pintype "bidirectional"))
    )
    (net (code "147") (name "/XL.PADDR14") (class "Default")
      (node (ref "U76") (pin "14") (pinfunction "1B10_14") (pintype "bidirectional"))
    )
    (net (code "148") (name "/XL.PADDR15") (class "Default")
      (node (ref "U76") (pin "15") (pinfunction "2B1_15") (pintype "bidirectional"))
    )
    (net (code "149") (name "/XL.PADDR16") (class "Default")
      (node (ref "U76") (pin "16") (pinfunction "2B2_16") (pintype "bidirectional"))
    )
    (net (code "150") (name "/XL.PADDR17") (class "Default")
      (node (ref "U76") (pin "17") (pinfunction "2B3_17") (pintype "bidirectional"))
    )
    (net (code "151") (name "/XL.PADDR18") (class "Default")
      (node (ref "U76") (pin "19") (pinfunction "2B4_19") (pintype "bidirectional"))
    )
    (net (code "152") (name "/XL.PADDR19") (class "Default")
      (node (ref "U76") (pin "20") (pinfunction "2B5_20") (pintype "bidirectional"))
    )
    (net (code "153") (name "/XL.PADDR20") (class "Default")
      (node (ref "U76") (pin "21") (pinfunction "2B6_21") (pintype "bidirectional"))
    )
    (net (code "154") (name "/XL.PADDR21") (class "Default")
      (node (ref "U76") (pin "23") (pinfunction "2B7_23") (pintype "bidirectional"))
    )
    (net (code "155") (name "/XL.PADDR22") (class "Default")
      (node (ref "U76") (pin "24") (pinfunction "2B8_24") (pintype "bidirectional"))
    )
    (net (code "156") (name "/XL.PADDR23") (class "Default")
      (node (ref "U80") (pin "2") (pinfunction "1B1_2") (pintype "bidirectional"))
    )
    (net (code "157") (name "/XL.PADDR24") (class "Default")
      (node (ref "U76") (pin "26") (pinfunction "2B9_26") (pintype "bidirectional"))
    )
    (net (code "158") (name "/XL.PADDR25") (class "Default")
      (node (ref "U76") (pin "27") (pinfunction "2B10_27") (pintype "bidirectional"))
    )
    (net (code "159") (name "/XL.PADDR26") (class "Default")
      (node (ref "U80") (pin "3") (pinfunction "1B2_3") (pintype "bidirectional"))
    )
    (net (code "160") (name "/XL.PADDR27") (class "Default")
      (node (ref "U80") (pin "5") (pinfunction "1B3_5") (pintype "bidirectional"))
    )
    (net (code "161") (name "/XL.PADDR28") (class "Default")
      (node (ref "U80") (pin "6") (pinfunction "1B4_6") (pintype "bidirectional"))
    )
    (net (code "162") (name "/XL.PADDR29") (class "Default")
      (node (ref "U80") (pin "8") (pinfunction "1B5_8") (pintype "bidirectional"))
    )
    (net (code "164") (name "/XL.PBEn0") (class "Default")
      (node (ref "U80") (pin "13") (pinfunction "1B9_13") (pintype "bidirectional"))
    )
    (net (code "165") (name "/XL.PBEn1") (class "Default")
      (node (ref "U80") (pin "12") (pinfunction "1B8_12") (pintype "bidirectional"))
    )
    (net (code "166") (name "/XL.PBEn2") (class "Default")
      (node (ref "U80") (pin "10") (pinfunction "1B7_10") (pintype "bidirectional"))
    )
    (net (code "167") (name "/XL.PBEn3") (class "Default")
      (node (ref "U80") (pin "9") (pinfunction "1B6_9") (pintype "bidirectional"))
    )
    (net (code "169") (name "/XL.PBLASTn") (class "Default")
      (node (ref "U80") (pin "16") (pinfunction "2B2_16") (pintype "bidirectional"))
    )
    (net (code "170") (name "/XL.PCSn0") (class "Default")
      (node (ref "TP43") (pin "1") (pinfunction "1_1") (pintype "passive"))
      (node (ref "U80") (pin "19") (pinfunction "2B4_19") (pintype "bidirectional"))
    )
    (net (code "171") (name "/XL.PCSn1") (class "Default")
      (node (ref "U80") (pin "17") (pinfunction "2B3_17") (pintype "bidirectional"))
    )
    (net (code "172") (name "/XL.PCSn2") (class "Default")
      (node (ref "U80") (pin "20") (pinfunction "2B5_20") (pintype "bidirectional"))
    )
    (net (code "174") (name "/XL.PDATA0") (class "Default")
      (node (ref "U81") (pin "2") (pinfunction "1B1_2") (pintype "bidirectional"))
    )
    (net (code "175") (name "/XL.PDATA1") (class "Default")
      (node (ref "U81") (pin "3") (pinfunction "1B2_3") (pintype "bidirectional"))
    )
    (net (code "176") (name "/XL.PDATA2") (class "Default")
      (node (ref "U81") (pin "5") (pinfunction "1B3_5") (pintype "bidirectional"))
    )
    (net (code "177") (name "/XL.PDATA3") (class "Default")
      (node (ref "U81") (pin "6") (pinfunction "1B4_6") (pintype "bidirectional"))
    )
    (net (code "178") (name "/XL.PDATA4") (class "Default")
      (node (ref "U81") (pin "8") (pinfunction "1B5_8") (pintype "bidirectional"))
    )
    (net (code "179") (name "/XL.PDATA5") (class "Default")
      (node (ref "U81") (pin "9") (pinfunction "1B6_9") (pintype "bidirectional"))
    )
    (net (code "180") (name "/XL.PDATA6") (class "Default")
      (node (ref "U81") (pin "11") (pinfunction "1B7_11") (pintype "bidirectional"))
    )
    (net (code "181") (name "/XL.PDATA7") (class "Default")
      (node (ref "U81") (pin "12") (pinfunction "1B8_12") (pintype "bidirectional"))
    )
    (net (code "182") (name "/XL.PDATA8") (class "Default")
      (node (ref "U81") (pin "13") (pinfunction "2B1_13") (pintype "bidirectional"))
    )
    (net (code "183") (name "/XL.PDATA9") (class "Default")
      (node (ref "U81") (pin "14") (pinfunction "2B2_14") (pintype "bidirectional"))
    )
    (net (code "184") (name "/XL.PDATA10") (class "Default")
      (node (ref "U81") (pin "16") (pinfunction "2B3_16") (pintype "bidirectional"))
    )
    (net (code "185") (name "/XL.PDATA11") (class "Default")
      (node (ref "U81") (pin "17") (pinfunction "2B4_17") (pintype "bidirectional"))
    )
    (net (code "186") (name "/XL.PDATA12") (class "Default")
      (node (ref "U81") (pin "19") (pinfunction "2B5_19") (pintype "bidirectional"))
    )
    (net (code "187") (name "/XL.PDATA13") (class "Default")
      (node (ref "U81") (pin "20") (pinfunction "2B6_20") (pintype "bidirectional"))
    )
    (net (code "188") (name "/XL.PDATA14") (class "Default")
      (node (ref "U81") (pin "22") (pinfunction "2B7_22") (pintype "bidirectional"))
    )
    (net (code "189") (name "/XL.PDATA15") (class "Default")
      (node (ref "U81") (pin "23") (pinfunction "2B8_23") (pintype "bidirectional"))
    )
    (net (code "190") (name "/XL.PDATA16") (class "Default")
      (node (ref "U78") (pin "2") (pinfunction "1B1_2") (pintype "bidirectional"))
    )
    (net (code "191") (name "/XL.PDATA17") (class "Default")
      (node (ref "U78") (pin "3") (pinfunction "1B2_3") (pintype "bidirectional"))
    )
    (net (code "192") (name "/XL.PDATA18") (class "Default")
      (node (ref "U78") (pin "5") (pinfunction "1B3_5") (pintype "bidirectional"))
    )
    (net (code "193") (name "/XL.PDATA19") (class "Default")
      (node (ref "U78") (pin "6") (pinfunction "1B4_6") (pintype "bidirectional"))
    )
    (net (code "194") (name "/XL.PDATA20") (class "Default")
      (node (ref "U78") (pin "8") (pinfunction "1B5_8") (pintype "bidirectional"))
    )
    (net (code "195") (name "/XL.PDATA21") (class "Default")
      (node (ref "U78") (pin "9") (pinfunction "1B6_9") (pintype "bidirectional"))
    )
    (net (code "196") (name "/XL.PDATA22") (class "Default")
      (node (ref "U78") (pin "11") (pinfunction "1B7_11") (pintype "bidirectional"))
    )
    (net (code "197") (name "/XL.PDATA23") (class "Default")
      (node (ref "U78") (pin "12") (pinfunction "1B8_12") (pintype "bidirectional"))
    )
    (net (code "198") (name "/XL.PDATA24") (class "Default")
      (node (ref "U78") (pin "13") (pinfunction "2B1_13") (pintype "bidirectional"))
    )
    (net (code "199") (name "/XL.PDATA25") (class "Default")
      (node (ref "U78") (pin "14") (pinfunction "2B2_14") (pintype "bidirectional"))
    )
    (net (code "200") (name "/XL.PDATA26") (class "Default")
      (node (ref "U78") (pin "16") (pinfunction "2B3_16") (pintype "bidirectional"))
    )
    (net (code "201") (name "/XL.PDATA27") (class "Default")
      (node (ref "U78") (pin "17") (pinfunction "2B4_17") (pintype "bidirectional"))
    )
    (net (code "202") (name "/XL.PDATA28") (class "Default")
      (node (ref "U78") (pin "19") (pinfunction "2B5_19") (pintype "bidirectional"))
    )
    (net (code "203") (name "/XL.PDATA29") (class "Default")
      (node (ref "U78") (pin "20") (pinfunction "2B6_20") (pintype "bidirectional"))
    )
    (net (code "204") (name "/XL.PDATA30") (class "Default")
      (node (ref "U78") (pin "22") (pinfunction "2B7_22") (pintype "bidirectional"))
    )
    (net (code "205") (name "/XL.PDATA31") (class "Default")
      (node (ref "TP42") (pin "1") (pinfunction "1_1") (pintype "passive"))
      (node (ref "U78") (pin "23") (pinfunction "2B8_23") (pintype "bidirectional"))
    )
    (net (code "207") (name "/XL.PERCLK") (class "Default")
      (node (ref "C169") (pin "2") (pinfunction "2_2") (pintype "passive"))
      (node (ref "R463") (pin "2") (pinfunction "2_2") (pintype "passive"))
      (node (ref "R470") (pin "2") (pinfunction "2_2") (pintype "passive"))
      (node (ref "R65") (pin "1") (pinfunction "1_1") (pintype "passive"))
      (node (ref "R66") (pin "2") (pinfunction "2_2") (pintype "passive"))
      (node (ref "TP41") (pin "1") (pinfunction "1_1") (pintype "passive"))
    )
    (net (code "208") (name "/XL.POEn") (class "Default")
      (node (ref "U80") (pin "14") (pinfunction "1B10_14") (pintype "bidirectional"))
    )
    (net (code "209") (name "/XL.PRDY") (class "Default")
      (node (ref "R230") (pin "1") (pinfunction "1_1") (pintype "passive"))
      (node (ref "U86") (pin "1") (pinfunction "A_1") (pintype "passive"))
    )
    (net (code "210") (name "/XL.PWRn") (class "Default")
      (node (ref "U80") (pin "15") (pinfunction "2B1_15") (pintype "bidirectional"))
    )
    (net (code "213") (name "1V5") (class "Default")
      (node (ref "R476") (pin "2") (pinfunction "2_2") (pintype "passive"))
      (node (ref "U75") (pin "1") (pinfunction "VCCA_1") (pintype "power_in"))
      (node (ref "U75") (pin "5") (pinfunction "DIR_5") (pintype "input"))
    )
    (net (code "214") (name "2V5") (class "Default")
      (node (ref "C53") (pin "2") (pinfunction "2_2") (pintype "passive"))
      (node (ref "C735") (pin "2") (pinfunction "2_2") (pintype "passive"))
      (node (ref "C736") (pin "2") (pinfunction "2_2") (pintype "passive"))
      (node (ref "C739") (pin "2") (pinfunction "2_2") (pintype "passive"))
      (node (ref "C740") (pin "2") (pinfunction "2_2") (pintype "passive"))
      (node (ref "C745") (pin "2") (pinfunction "2_2") (pintype "passive"))
      (node (ref "C746") (pin "2") (pinfunction "2_2") (pintype "passive"))
      (node (ref "C749") (pin "2") (pinfunction "2_2") (pintype "passive"))
      (node (ref "C750") (pin "2") (pinfunction "2_2") (pintype "passive"))
      (node (ref "R65") (pin "2") (pinfunction "2_2") (pintype "passive"))
      (node (ref "U73") (pin "6") (pinfunction "VCCB_6") (pintype "power_in"))
      (node (ref "U74") (pin "5") (pinfunction "VCC_5") (pintype "power_in"))
      (node (ref "U76") (pin "22") (pinfunction "VCCB_22") (pintype "power_in"))
      (node (ref "U76") (pin "7") (pinfunction "VCCB_7") (pintype "power_in"))
      (node (ref "U78") (pin "18") (pinfunction "VCCB_18") (pintype "power_in"))
      (node (ref "U78") (pin "7") (pinfunction "VCCB_7") (pintype "power_in"))
      (node (ref "U80") (pin "22") (pinfunction "VCCB_22") (pintype "power_in"))
      (node (ref "U80") (pin "7") (pinfunction "VCCB_7") (pintype "power_in"))
      (node (ref "U81") (pin "18") (pinfunction "VCCB_18") (pintype "power_in"))
      (node (ref "U81") (pin "7") (pinfunction "VCCB_7") (pintype "power_in"))
    )
    (net (code "215") (name "3V3") (class "Default")
      (node (ref "C489") (pin "2") (pinfunction "2_2") (pintype "passive"))
      (node (ref "C490") (pin "2") (pinfunction "2_2") (pintype "passive"))
      (node (ref "C732") (pin "2") (pinfunction "2_2") (pintype "passive"))
      (node (ref "C733") (pin "2") (pinfunction "2_2") (pintype "passive"))
      (node (ref "C734") (pin "2") (pinfunction "2_2") (pintype "passive"))
      (node (ref "C737") (pin "2") (pinfunction "2_2") (pintype "passive"))
      (node (ref "C738") (pin "2") (pinfunction "2_2") (pintype "passive"))
      (node (ref "C741") (pin "2") (pinfunction "2_2") (pintype "passive"))
      (node (ref "C742") (pin "2") (pinfunction "2_2") (pintype "passive"))
      (node (ref "C743") (pin "2") (pinfunction "2_2") (pintype "passive"))
      (node (ref "C744") (pin "2") (pinfunction "2_2") (pintype "passive"))
      (node (ref "C747") (pin "2") (pinfunction "2_2") (pintype "passive"))
      (node (ref "C748") (pin "2") (pinfunction "2_2") (pintype "passive"))
      (node (ref "R230") (pin "2") (pinfunction "2_2") (pintype "passive"))
      (node (ref "R269") (pin "2") (pinfunction "2_2") (pintype "passive"))
      (node (ref "R468") (pin "2") (pinfunction "2_2") (pintype "passive"))
      (node (ref "U52") (pin "5") (pinfunction "VCC_5") (pintype "passive"))
      (node (ref "U53") (pin "5") (pinfunction "VCC_5") (pintype "passive"))
      (node (ref "U73") (pin "1") (pinfunction "VCCA_1") (pintype "power_in"))
      (node (ref "U73") (pin "5") (pinfunction "DIR_5") (pintype "input"))
      (node (ref "U75") (pin "6") (pinfunction "VCCB_6") (pintype "power_in"))
      (node (ref "U76") (pin "1") (pinfunction "1DIR_1") (pintype "input"))
      (node (ref "U76") (pin "28") (pinfunction "2DIR_28") (pintype "input"))
      (node (ref "U76") (pin "35") (pinfunction "VCCA_35") (pintype "power_in"))
      (node (ref "U76") (pin "50") (pinfunction "VCCA_50") (pintype "power_in"))
      (node (ref "U77") (pin "20") (pinfunction "VCC_20") (pintype "power_in"))
      (node (ref "U78") (pin "31") (pinfunction "VCCA_31") (pintype "power_in"))
      (node (ref "U78") (pin "42") (pinfunction "VCCA_42") (pintype "power_in"))
      (node (ref "U79") (pin "20") (pinfunction "VCC_20") (pintype "power_in"))
      (node (ref "U80") (pin "1") (pinfunction "1DIR_1") (pintype "input"))
      (node (ref "U80") (pin "28") (pinfunction "2DIR_28") (pintype "input"))
      (node (ref "U80") (pin "35") (pinfunction "VCCA_35") (pintype "power_in"))
      (node (ref "U80") (pin "50") (pinfunction "VCCA_50") (pintype "power_in"))
      (node (ref "U81") (pin "31") (pinfunction "VCCA_31") (pintype "power_in"))
      (node (ref "U81") (pin "42") (pinfunction "VCCA_42") (pintype "power_in"))
      (node (ref "U82") (pin "20") (pinfunction "VCC_20") (pintype "power_in"))
      (node (ref "U86") (pin "5") (pinfunction "VCC_5") (pintype "passive"))
    )
    (net (code "216") (name "3V3AUX") (class "Default")
      (node (ref "R49") (pin "2") (pinfunction "2_2") (pintype "passive"))
      (node (ref "R50") (pin "2") (pinfunction "2_2") (pintype "passive"))
    )
    (net (code "217") (name "GND") (class "Default")
      (node (ref "C169") (pin "1") (pinfunction "1_1") (pintype "passive"))
      (node (ref "C489") (pin "1") (pinfunction "1_1") (pintype "passive"))
      (node (ref "C490") (pin "1") (pinfunction "1_1") (pintype "passive"))
      (node (ref "C53") (pin "1") (pinfunction "1_1") (pintype "passive"))
      (node (ref "C730") (pin "1") (pinfunction "1_1") (pintype "passive"))
      (node (ref "C731") (pin "1") (pinfunction "1_1") (pintype "passive"))
      (node (ref "C732") (pin "1") (pinfunction "1_1") (pintype "passive"))
      (node (ref "C733") (pin "1") (pinfunction "1_1") (pintype "passive"))
      (node (ref "C734") (pin "1") (pinfunction "1_1") (pintype "passive"))
      (node (ref "C735") (pin "1") (pinfunction "1_1") (pintype "passive"))
      (node (ref "C736") (pin "1") (pinfunction "1_1") (pintype "passive"))
      (node (ref "C737") (pin "1") (pinfunction "1_1") (pintype "passive"))
      (node (ref "C738") (pin "1") (pinfunction "1_1") (pintype "passive"))
      (node (ref "C739") (pin "1") (pinfunction "1_1") (pintype "passive"))
      (node (ref "C740") (pin "1") (pinfunction "1_1") (pintype "passive"))
      (node (ref "C741") (pin "1") (pinfunction "1_1") (pintype "passive"))
      (node (ref "C742") (pin "1") (pinfunction "1_1") (pintype "passive"))
      (node (ref "C743") (pin "1") (pinfunction "1_1") (pintype "passive"))
      (node (ref "C744") (pin "1") (pinfunction "1_1") (pintype "passive"))
      (node (ref "C745") (pin "1") (pinfunction "1_1") (pintype "passive"))
      (node (ref "C746") (pin "1") (pinfunction "1_1") (pintype "passive"))
      (node (ref "C747") (pin "1") (pinfunction "1_1") (pintype "passive"))
      (node (ref "C748") (pin "1") (pinfunction "1_1") (pintype "passive"))
      (node (ref "C749") (pin "1") (pinfunction "1_1") (pintype "passive"))
      (node (ref "C750") (pin "1") (pinfunction "1_1") (pintype "passive"))
      (node (ref "P17") (pin "16") (pinfunction "B16_16") (pintype "output"))
      (node (ref "R252") (pin "1") (pinfunction "1_1") (pintype "passive"))
      (node (ref "R66") (pin "1") (pinfunction "1_1") (pintype "passive"))
      (node (ref "U52") (pin "2") (pinfunction "GND_2") (pintype "passive"))
      (node (ref "U53") (pin "2") (pinfunction "GND_2") (pintype "passive"))
      (node (ref "U73") (pin "2") (pinfunction "GND_2") (pintype "input"))
      (node (ref "U74") (pin "3") (pinfunction "GND_3") (pintype "power_in"))
      (node (ref "U75") (pin "2") (pinfunction "GND_2") (pintype "input"))
      (node (ref "U76") (pin "11") (pinfunction "GND_11") (pintype "power_in"))
      (node (ref "U76") (pin "18") (pinfunction "GND_18") (pintype "power_in"))
      (node (ref "U76") (pin "25") (pinfunction "GND_25") (pintype "power_in"))
      (node (ref "U76") (pin "29") (pinfunction "2OEn_29") (pintype "input"))
      (node (ref "U76") (pin "32") (pinfunction "GND_32") (pintype "power_in"))
      (node (ref "U76") (pin "39") (pinfunction "GND_39") (pintype "power_in"))
      (node (ref "U76") (pin "4") (pinfunction "GND_4") (pintype "power_in"))
      (node (ref "U76") (pin "46") (pinfunction "GND_46") (pintype "power_in"))
      (node (ref "U76") (pin "53") (pinfunction "GND_53") (pintype "power_in"))
      (node (ref "U76") (pin "56") (pinfunction "1OEn_56") (pintype "input"))
      (node (ref "U77") (pin "1") (pinfunction "1OEn_1") (pintype "input"))
      (node (ref "U77") (pin "10") (pinfunction "GND_10") (pintype "power_in"))
      (node (ref "U77") (pin "19") (pinfunction "2OEn_19") (pintype "input"))
      (node (ref "U78") (pin "10") (pinfunction "GND_10") (pintype "power_in"))
      (node (ref "U78") (pin "15") (pinfunction "GND_15") (pintype "power_in"))
      (node (ref "U78") (pin "21") (pinfunction "GND_21") (pintype "power_in"))
      (node (ref "U78") (pin "25") (pinfunction "2OEn_25") (pintype "input"))
      (node (ref "U78") (pin "28") (pinfunction "GND_28") (pintype "power_in"))
      (node (ref "U78") (pin "34") (pinfunction "GND_34") (pintype "power_in"))
      (node (ref "U78") (pin "39") (pinfunction "GND_39") (pintype "power_in"))
      (node (ref "U78") (pin "4") (pinfunction "GND_4") (pintype "power_in"))
      (node (ref "U78") (pin "45") (pinfunction "GND_45") (pintype "power_in"))
      (node (ref "U78") (pin "48") (pinfunction "1OEn_48") (pintype "input"))
      (node (ref "U79") (pin "1") (pinfunction "1OEn_1") (pintype "input"))
      (node (ref "U79") (pin "10") (pinfunction "GND_10") (pintype "power_in"))
      (node (ref "U79") (pin "19") (pinfunction "2OEn_19") (pintype "input"))
      (node (ref "U80") (pin "11") (pinfunction "GND_11") (pintype "power_in"))
      (node (ref "U80") (pin "18") (pinfunction "GND_18") (pintype "power_in"))
      (node (ref "U80") (pin "25") (pinfunction "GND_25") (pintype "power_in"))
      (node (ref "U80") (pin "29") (pinfunction "2OEn_29") (pintype "input"))
      (node (ref "U80") (pin "30") (pinfunction "2A10_30") (pintype "bidirectional"))
      (node (ref "U80") (pin "31") (pinfunction "2A9_31") (pintype "bidirectional"))
      (node (ref "U80") (pin "32") (pinfunction "GND_32") (pintype "power_in"))
      (node (ref "U80") (pin "33") (pinfunction "2A8_33") (pintype "bidirectional"))
      (node (ref "U80") (pin "34") (pinfunction "2A7_34") (pintype "bidirectional"))
      (node (ref "U80") (pin "36") (pinfunction "2A6_36") (pintype "bidirectional"))
      (node (ref "U80") (pin "39") (pinfunction "GND_39") (pintype "power_in"))
      (node (ref "U80") (pin "4") (pinfunction "GND_4") (pintype "power_in"))
      (node (ref "U80") (pin "46") (pinfunction "GND_46") (pintype "power_in"))
      (node (ref "U80") (pin "53") (pinfunction "GND_53") (pintype "power_in"))
      (node (ref "U80") (pin "56") (pinfunction "1OEn_56") (pintype "input"))
      (node (ref "U81") (pin "10") (pinfunction "GND_10") (pintype "power_in"))
      (node (ref "U81") (pin "15") (pinfunction "GND_15") (pintype "power_in"))
      (node (ref "U81") (pin "21") (pinfunction "GND_21") (pintype "power_in"))
      (node (ref "U81") (pin "25") (pinfunction "2OEn_25") (pintype "input"))
      (node (ref "U81") (pin "28") (pinfunction "GND_28") (pintype "power_in"))
      (node (ref "U81") (pin "34") (pinfunction "GND_34") (pintype "power_in"))
      (node (ref "U81") (pin "39") (pinfunction "GND_39") (pintype "power_in"))
      (node (ref "U81") (pin "4") (pinfunction "GND_4") (pintype "power_in"))
      (node (ref "U81") (pin "45") (pinfunction "GND_45") (pintype "power_in"))
      (node (ref "U81") (pin "48") (pinfunction "1OEn_48") (pintype "input"))
      (node (ref "U82") (pin "1") (pinfunction "1OEn_1") (pintype "input"))
      (node (ref "U82") (pin "10") (pinfunction "GND_10") (pintype "power_in"))
      (node (ref "U82") (pin "15") (pinfunction "2A3_15") (pintype "input"))
      (node (ref "U82") (pin "17") (pinfunction "2A4_17") (pintype "input"))
      (node (ref "U82") (pin "19") (pinfunction "2OEn_19") (pintype "input"))
      (node (ref "U86") (pin "3") (pinfunction "GND_3") (pintype "passive"))
    )
    (net (code "218") (name "Net-(P17-A1)") (class "Default")
      (node (ref "P17") (pin "1") (pinfunction "A1_1") (pintype "output"))
      (node (ref "R471") (pin "2") (pinfunction "2_2") (pintype "passive"))
    )
    (net (code "219") (name "Net-(P17-A3)") (class "Default")
      (node (ref "P17") (pin "3") (pinfunction "A3_3") (pintype "output"))
      (node (ref "R472") (pin "2") (pinfunction "2_2") (pintype "passive"))
    )
    (net (code "220") (name "Net-(P17-A7)") (class "Default")
      (node (ref "P17") (pin "7") (pinfunction "A7_7") (pintype "output"))
      (node (ref "R474") (pin "2") (pinfunction "2_2") (pintype "passive"))
    )
    (net (code "221") (name "Net-(P17-A9)") (class "Default")
      (node (ref "P17") (pin "9") (pinfunction "A9_9") (pintype "output"))
      (node (ref "R475") (pin "2") (pinfunction "2_2") (pintype "passive"))
    )
    (net (code "222") (name "Net-(P17-B4)") (class "Default")
      (node (ref "P17") (pin "4") (pinfunction "B4_4") (pintype "output"))
      (node (ref "R473") (pin "1") (pinfunction "1_1") (pintype "passive"))
    )
    (net (code "223") (name "Net-(U73-B)") (class "Default")
      (node (ref "R463") (pin "1") (pinfunction "1_1") (pintype "passive"))
      (node (ref "U73") (pin "4") (pinfunction "B_4") (pintype "bidirectional"))
    )
    (net (code "224") (name "Net-(U74-Y)") (class "Default")
      (node (ref "R470") (pin "1") (pinfunction "1_1") (pintype "passive"))
      (node (ref "U74") (pin "4") (pinfunction "Y_4") (pintype "output"))
    )
    (net (code "225") (name "Net-(U78-1DIR)") (class "Default")
      (node (ref "R487") (pin "2") (pinfunction "2_2") (pintype "passive"))
      (node (ref "U78") (pin "1") (pinfunction "1DIR_1") (pintype "input"))
      (node (ref "U78") (pin "24") (pinfunction "2DIR_24") (pintype "input"))
    )
    (net (code "226") (name "Net-(U81-1DIR)") (class "Default")
      (node (ref "R490") (pin "2") (pinfunction "2_2") (pintype "passive"))
      (node (ref "U81") (pin "1") (pinfunction "1DIR_1") (pintype "input"))
      (node (ref "U81") (pin "24") (pinfunction "2DIR_24") (pintype "input"))
    )
    (net (code "227") (name "VCC_JTAG") (class "Default")
      (node (ref "C730") (pin "2") (pinfunction "2_2") (pintype "passive"))
      (node (ref "C731") (pin "2") (pinfunction "2_2") (pintype "passive"))
      (node (ref "P17") (pin "6") (pinfunction "B6_6") (pintype "output"))
      (node (ref "R468") (pin "1") (pinfunction "1_1") (pintype "passive"))
    )
    (net (code "228") (name "unconnected-(P17-A5-Pad5)") (class "Default")
      (node (ref "P17") (pin "5") (pinfunction "A5_5") (pintype "output+no_connect"))
    )
    (net (code "229") (name "unconnected-(P17-A13-Pad13)") (class "Default")
      (node (ref "P17") (pin "13") (pinfunction "A13_13") (pintype "output+no_connect"))
    )
    (net (code "230") (name "unconnected-(P17-A15-Pad15)") (class "Default")
      (node (ref "P17") (pin "15") (pinfunction "A15_15") (pintype "output+no_connect"))
    )
    (net (code "231") (name "unconnected-(P17-B2-Pad2)") (class "Default")
      (node (ref "P17") (pin "2") (pinfunction "B2_2") (pintype "output+no_connect"))
    )
    (net (code "232") (name "unconnected-(P17-B8-Pad8)") (class "Default")
      (node (ref "P17") (pin "8") (pinfunction "B8_8") (pintype "output+no_connect"))
    )
    (net (code "233") (name "unconnected-(P17-B10-Pad10)") (class "Default")
      (node (ref "P17") (pin "10") (pinfunction "B10_10") (pintype "output+no_connect"))
    )
    (net (code "234") (name "unconnected-(P17-B12-Pad12)") (class "Default")
      (node (ref "P17") (pin "12") (pinfunction "B12_12") (pintype "output+no_connect"))
    )
    (net (code "235") (name "unconnected-(P17-B14-Pad14)") (class "Default")
      (node (ref "P17") (pin "14") (pinfunction "B14_14") (pintype "output+no_connect"))
    )
    (net (code "236") (name "unconnected-(U74-NC-Pad1)") (class "Default")
      (node (ref "U74") (pin "1") (pinfunction "NC_1") (pintype "passive+no_connect"))
    )
    (net (code "237") (name "unconnected-(U80-2B6-Pad21)") (class "Default")
      (node (ref "U80") (pin "21") (pinfunction "2B6_21") (pintype "bidirectional+no_connect"))
    )
    (net (code "238") (name "unconnected-(U80-2B7-Pad23)") (class "Default")
      (node (ref "U80") (pin "23") (pinfunction "2B7_23") (pintype "bidirectional+no_connect"))
    )
    (net (code "239") (name "unconnected-(U80-2B8-Pad24)") (class "Default")
      (node (ref "U80") (pin "24") (pinfunction "2B8_24") (pintype "bidirectional+no_connect"))
    )
    (net (code "240") (name "unconnected-(U80-2B9-Pad26)") (class "Default")
      (node (ref "U80") (pin "26") (pinfunction "2B9_26") (pintype "bidirectional+no_connect"))
    )
    (net (code "241") (name "unconnected-(U80-2B10-Pad27)") (class "Default")
      (node (ref "U80") (pin "27") (pinfunction "2B10_27") (pintype "bidirectional+no_connect"))
    )
    (net (code "242") (name "unconnected-(U82-2Y3-Pad5)") (class "Default")
      (node (ref "U82") (pin "5") (pinfunction "2Y3_5") (pintype "output+no_connect"))
    )
    (net (code "243") (name "unconnected-(U82-2Y4-Pad3)") (class "Default")
      (node (ref "U82") (pin "3") (pinfunction "2Y4_3") (pintype "output+no_connect"))
    )
  )
)
